# nrf_ard.net
KiCad netlist of a schematic drawn in EAGLE
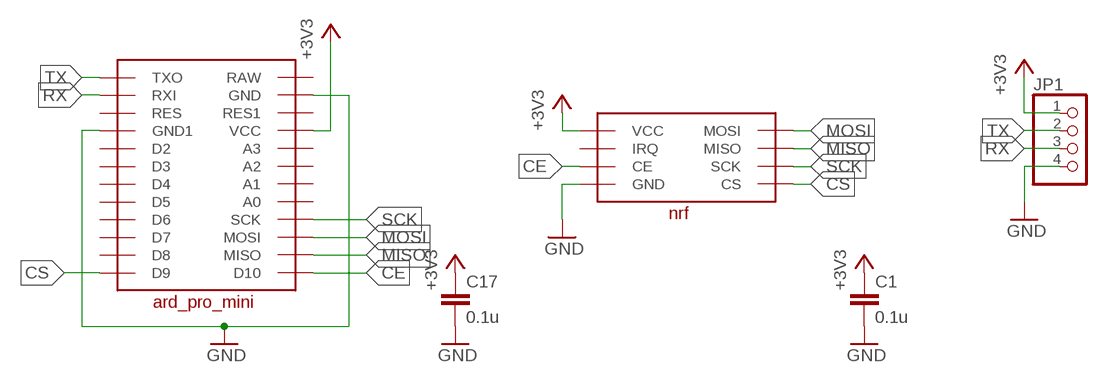
[diagram p0: schematic, sheet 1]

(export (version "E")
  (design (tool "Eeschema 10.0.6"))
  (components
    (comp (ref "C1")
      (value "0.1u")
      (footprint "eagle-import:C0603K")
      (libsource (lib "eagle-import") (part "C-EUC0603K"))
    )
    (comp (ref "C17")
      (value "0.1u")
      (footprint "eagle-import:C0603K")
      (libsource (lib "eagle-import") (part "C-EUC0603K"))
    )
    (comp (ref "JP1")
      (value "PINHD-1X4")
      (footprint "eagle-import:1X04")
      (libsource (lib "eagle-import") (part "PINHD-1X4"))
    )
    (comp (ref "U$1")
      (value "ARD_PRO_MINI")
      (footprint "eagle-import:ARD_PRO_MINI")
      (libsource (lib "eagle-import") (part "ARD_PRO_MINI"))
    )
    (comp (ref "U$2")
      (value "NRF")
      (footprint "eagle-import:NRF")
      (libsource (lib "eagle-import") (part "NRF"))
    )
  )
  (nets
    (net (code "1") (name "+3V3") (class "Default")
      (node (ref "C1") (pin "1") (pinfunction "1_1") (pintype "passive"))
      (node (ref "C17") (pin "1") (pinfunction "1_1") (pintype "passive"))
      (node (ref "JP1") (pin "1") (pinfunction "1_1") (pintype "passive"))
      (node (ref "U$1") (pin "VCC") (pinfunction "VCC_VCC") (pintype "bidirectional"))
      (node (ref "U$2") (pin "VCC") (pinfunction "VCC_VCC") (pintype "bidirectional"))
    )
    (net (code "2") (name "CE") (class "Default")
      (node (ref "U$1") (pin "D10") (pinfunction "D10_D10") (pintype "bidirectional"))
      (node (ref "U$2") (pin "CE") (pinfunction "CE_CE") (pintype "bidirectional"))
    )
    (net (code "3") (name "CS") (class "Default")
      (node (ref "U$1") (pin "D9") (pinfunction "D9_D9") (pintype "bidirectional"))
      (node (ref "U$2") (pin "CS") (pinfunction "CS_CS") (pintype "bidirectional"))
    )
    (net (code "4") (name "GND") (class "Default")
      (node (ref "C1") (pin "2") (pinfunction "2_2") (pintype "passive"))
      (node (ref "C17") (pin "2") (pinfunction "2_2") (pintype "passive"))
      (node (ref "JP1") (pin "4") (pinfunction "4_4") (pintype "passive"))
      (node (ref "U$1") (pin "GND1") (pinfunction "GND_GND1") (pintype "bidirectional"))
      (node (ref "U$1") (pin "GND2") (pinfunction "GND1_GND2") (pintype "bidirectional"))
      (node (ref "U$2") (pin "GND") (pinfunction "GND_GND") (pintype "bidirectional"))
    )
    (net (code "5") (name "MISO") (class "Default")
      (node (ref "U$1") (pin "MISO") (pinfunction "MISO_MISO") (pintype "bidirectional"))
      (node (ref "U$2") (pin "MISO") (pinfunction "MISO_MISO") (pintype "bidirectional"))
    )
    (net (code "6") (name "MOSI") (class "Default")
      (node (ref "U$1") (pin "MOSI") (pinfunction "MOSI_MOSI") (pintype "bidirectional"))
      (node (ref "U$2") (pin "MOSI") (pinfunction "MOSI_MOSI") (pintype "bidirectional"))
    )
    (net (code "7") (name "RX") (class "Default")
      (node (ref "JP1") (pin "3") (pinfunction "3_3") (pintype "passive"))
      (node (ref "U$1") (pin "RXI") (pinfunction "RXI_RXI") (pintype "bidirectional"))
    )
    (net (code "8") (name "SCK") (class "Default")
      (node (ref "U$1") (pin "SCK") (pinfunction "SCK_SCK") (pintype "bidirectional"))
      (node (ref "U$2") (pin "SCK") (pinfunction "SCK_SCK") (pintype "bidirectional"))
    )
    (net (code "9") (name "TX") (class "Default")
      (node (ref "JP1") (pin "2") (pinfunction "2_2") (pintype "passive"))
      (node (ref "U$1") (pin "TXO") (pinfunction "TXO_TXO") (pintype "bidirectional"))
    )
    (net (code "10") (name "unconnected-(U$1-PadA0)") (class "Default")
      (node (ref "U$1") (pin "A0") (pinfunction "A0_A0") (pintype "bidirectional"))
    )
    (net (code "11") (name "unconnected-(U$1-PadA1)") (class "Default")
      (node (ref "U$1") (pin "A1") (pinfunction "A1_A1") (pintype "bidirectional"))
    )
    (net (code "12") (name "unconnected-(U$1-PadA2)") (class "Default")
      (node (ref "U$1") (pin "A2") (pinfunction "A2_A2") (pintype "bidirectional"))
    )
    (net (code "13") (name "unconnected-(U$1-PadA3)") (class "Default")
      (node (ref "U$1") (pin "A3") (pinfunction "A3_A3") (pintype "bidirectional"))
    )
    (net (code "14") (name "unconnected-(U$1-PadD2)") (class "Default")
      (node (ref "U$1") (pin "D2") (pinfunction "D2_D2") (pintype "bidirectional"))
    )
    (net (code "15") (name "unconnected-(U$1-PadD3)") (class "Default")
      (node (ref "U$1") (pin "D3") (pinfunction "D3_D3") (pintype "bidirectional"))
    )
    (net (code "16") (name "unconnected-(U$1-PadD4)") (class "Default")
      (node (ref "U$1") (pin "D4") (pinfunction "D4_D4") (pintype "bidirectional"))
    )
    (net (code "17") (name "unconnected-(U$1-PadD5)") (class "Default")
      (node (ref "U$1") (pin "D5") (pinfunction "D5_D5") (pintype "bidirectional"))
    )
    (net (code "18") (name "unconnected-(U$1-PadD6)") (class "Default")
      (node (ref "U$1") (pin "D6") (pinfunction "D6_D6") (pintype "bidirectional"))
    )
    (net (code "19") (name "unconnected-(U$1-PadD7)") (class "Default")
      (node (ref "U$1") (pin "D7") (pinfunction "D7_D7") (pintype "bidirectional"))
    )
    (net (code "20") (name "unconnected-(U$1-PadD8)") (class "Default")
      (node (ref "U$1") (pin "D8") (pinfunction "D8_D8") (pintype "bidirectional"))
    )
    (net (code "21") (name "unconnected-(U$1-PadRAW)") (class "Default")
      (node (ref "U$1") (pin "RAW") (pinfunction "RAW_RAW") (pintype "bidirectional"))
    )
    (net (code "22") (name "unconnected-(U$1-RES-PadRES1)") (class "Default")
      (node (ref "U$1") (pin "RES1") (pinfunction "RES_RES1") (pintype "bidirectional"))
    )
    (net (code "23") (name "unconnected-(U$1-RES1-PadRST)") (class "Default")
      (node (ref "U$1") (pin "RST") (pinfunction "RES1_RST") (pintype "bidirectional"))
    )
    (net (code "24") (name "unconnected-(U$2-PadIRQ)") (class "Default")
      (node (ref "U$2") (pin "IRQ") (pinfunction "IRQ_IRQ") (pintype "bidirectional"))
    )
  )
)
